# Galvanometer.net
KiCad netlist of a schematic drawn in EAGLE
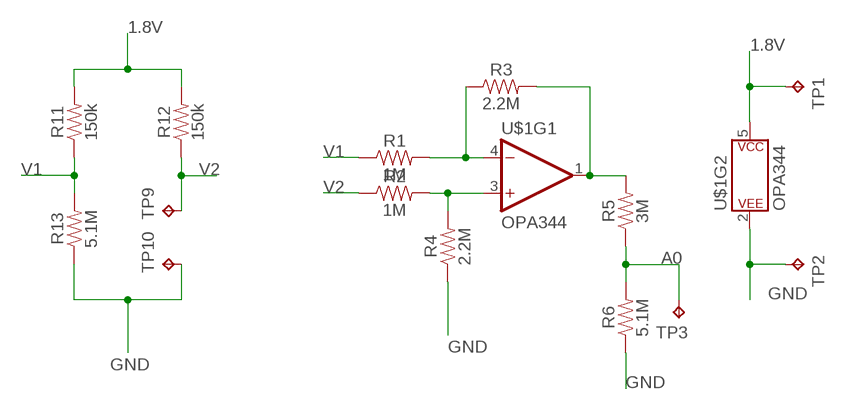
[diagram p0: schematic, sheet 1]

(export (version "E")
  (design (tool "Eeschema 10.0.6"))
  (components
    (comp (ref "R1")
      (value "1M")
      (footprint "eagle-import:0603")
      (libsource (lib "eagle-import") (part "RESISTOR0603"))
    )
    (comp (ref "R2")
      (value "1M")
      (footprint "eagle-import:0603")
      (libsource (lib "eagle-import") (part "RESISTOR0603"))
    )
    (comp (ref "R3")
      (value "2.2M")
      (footprint "eagle-import:0603")
      (libsource (lib "eagle-import") (part "RESISTOR0603"))
    )
    (comp (ref "R4")
      (value "2.2M")
      (footprint "eagle-import:0603")
      (libsource (lib "eagle-import") (part "RESISTOR0603"))
    )
    (comp (ref "R5")
      (value "3M")
      (footprint "eagle-import:0603")
      (libsource (lib "eagle-import") (part "RESISTOR0603"))
    )
    (comp (ref "R6")
      (value "5.1M")
      (footprint "eagle-import:0603")
      (libsource (lib "eagle-import") (part "RESISTOR0603"))
    )
    (comp (ref "R11")
      (value "150k")
      (footprint "eagle-import:0603")
      (libsource (lib "eagle-import") (part "10KOHM-0603-1/10W-1%"))
    )
    (comp (ref "R12")
      (value "150k")
      (footprint "eagle-import:0603")
      (libsource (lib "eagle-import") (part "10KOHM-0603-1/10W-1%"))
    )
    (comp (ref "R13")
      (value "5.1M")
      (footprint "eagle-import:0603")
      (libsource (lib "eagle-import") (part "10KOHM-0603-1/10W-1%"))
    )
    (comp (ref "TP1")
      (value "TPTP19R")
      (footprint "eagle-import:TP19R")
      (libsource (lib "eagle-import") (part "TPTP19R"))
    )
    (comp (ref "TP2")
      (value "TPTP19R")
      (footprint "eagle-import:TP19R")
      (libsource (lib "eagle-import") (part "TPTP19R"))
    )
    (comp (ref "TP3")
      (value "TPTP19R")
      (footprint "eagle-import:TP19R")
      (libsource (lib "eagle-import") (part "TPTP19R"))
    )
    (comp (ref "TP9")
      (value "TPTP19R")
      (footprint "eagle-import:TP19R")
      (libsource (lib "eagle-import") (part "TPTP19R"))
    )
    (comp (ref "TP10")
      (value "TPTP19R")
      (footprint "eagle-import:TP19R")
      (libsource (lib "eagle-import") (part "TPTP19R"))
    )
    (comp (ref "U$1")
      (value "OPA344")
      (footprint "eagle-import:SOT23-5")
      (libsource (lib "eagle-import") (part "OPA344"))
    )
  )
  (nets
    (net (code "1") (name "/1.8V") (class "Default")
      (node (ref "R11") (pin "2") (pinfunction "2_2") (pintype "passive"))
      (node (ref "R12") (pin "2") (pinfunction "2_2") (pintype "passive"))
      (node (ref "TP1") (pin "TP") (pinfunction "TP_TP") (pintype "input"))
      (node (ref "U$1") (pin "5") (pinfunction "P$V+_5") (pintype "bidirectional"))
    )
    (net (code "2") (name "/A0") (class "Default")
      (node (ref "R5") (pin "1") (pinfunction "1_1") (pintype "passive"))
      (node (ref "R6") (pin "2") (pinfunction "2_2") (pintype "passive"))
      (node (ref "TP3") (pin "TP") (pinfunction "TP_TP") (pintype "input"))
    )
    (net (code "3") (name "/GND") (class "Default")
      (node (ref "R13") (pin "1") (pinfunction "1_1") (pintype "passive"))
      (node (ref "R4") (pin "1") (pinfunction "1_1") (pintype "passive"))
      (node (ref "R6") (pin "1") (pinfunction "1_1") (pintype "passive"))
      (node (ref "TP10") (pin "TP") (pinfunction "TP_TP") (pintype "input"))
      (node (ref "TP2") (pin "TP") (pinfunction "TP_TP") (pintype "input"))
      (node (ref "U$1") (pin "2") (pinfunction "P$V-_2") (pintype "bidirectional"))
    )
    (net (code "4") (name "/V1") (class "Default")
      (node (ref "R1") (pin "1") (pinfunction "1_1") (pintype "passive"))
      (node (ref "R11") (pin "1") (pinfunction "1_1") (pintype "passive"))
      (node (ref "R13") (pin "2") (pinfunction "2_2") (pintype "passive"))
    )
    (net (code "5") (name "/V2") (class "Default")
      (node (ref "R12") (pin "1") (pinfunction "1_1") (pintype "passive"))
      (node (ref "R2") (pin "1") (pinfunction "1_1") (pintype "passive"))
      (node (ref "TP9") (pin "TP") (pinfunction "TP_TP") (pintype "input"))
    )
    (net (code "6") (name "Net-(U$1A-+IN)") (class "Default")
      (node (ref "R2") (pin "2") (pinfunction "2_2") (pintype "passive"))
      (node (ref "R4") (pin "2") (pinfunction "2_2") (pintype "passive"))
      (node (ref "U$1") (pin "3") (pinfunction "+IN_3") (pintype "input"))
    )
    (net (code "7") (name "Net-(U$1A--IN)") (class "Default")
      (node (ref "R1") (pin "2") (pinfunction "2_2") (pintype "passive"))
      (node (ref "R3") (pin "1") (pinfunction "1_1") (pintype "passive"))
      (node (ref "U$1") (pin "4") (pinfunction "-IN_4") (pintype "input"))
    )
    (net (code "8") (name "Net-(U$1A-OUT)") (class "Default")
      (node (ref "R3") (pin "2") (pinfunction "2_2") (pintype "passive"))
      (node (ref "R5") (pin "2") (pinfunction "2_2") (pintype "passive"))
      (node (ref "U$1") (pin "1") (pinfunction "OUT_1") (pintype "output"))
    )
  )
)
